# Power.net
KiCad netlist of a schematic drawn in Altium Designer
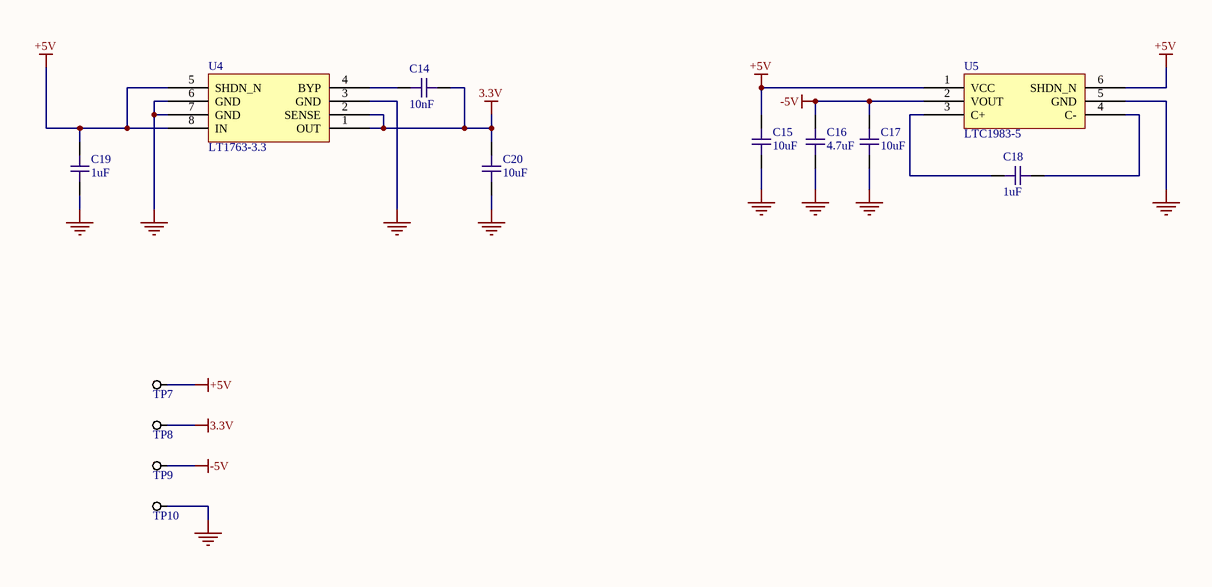
[diagram p0: Power.SchDoc]

(export (version "E")
  (design (tool "Eeschema 10.0.6"))
  (components
    (comp (ref "C14")
      (value "10nF")
      (footprint "C0402-IPC")
      (description "Chip Capacitor, 0402, 10nF, 16V, X7R")
      (fields (field (name "Comment") "C0402 10nF 16V X7R"))
      (libsource (lib "Capacitors") (part "C0402 10nF 16V X7R"))
    )
    (comp (ref "C15")
      (value "10uF")
      (footprint "C0402-HIGH-DENSITY")
      (description "Chip Capacitor, 0402, 10uF, 10V, X5R")
      (fields (field (name "Comment") "C0402 10uF 10V"))
      (libsource (lib "Capacitors") (part "C0402 10uF 10V"))
    )
    (comp (ref "C16")
      (value "4.7uF")
      (footprint "C0603-HIGH-DENSITY")
      (description "Chip Capacitor, 0603, 4.7uF, 25V, X5R")
      (fields (field (name "Comment") "4.7uF, 25V, X5R, 0603"))
      (libsource (lib "Capacitors") (part "C0603 4.7uF 25V X5R"))
    )
    (comp (ref "C17")
      (value "10uF")
      (footprint "C0402-HIGH-DENSITY")
      (description "Chip Capacitor, 0402, 10uF, 10V, X5R")
      (fields (field (name "Comment") "C0402 10uF 10V"))
      (libsource (lib "Capacitors") (part "C0402 10uF 10V"))
    )
    (comp (ref "C18")
      (value "1uF")
      (footprint "C0603-HIGH-DENSITY")
      (description "CAP CER 1UF 35V X5R 0603")
      (fields
        (field (name "MANUFACTURER") "Taiyo Yuden")
        (field (name "MANUFACTURER PART NUMBER") "GMK107BJ105MAHT")
      )
      (libsource (lib "AFE") (part "1uF 0603 35V X5R"))
    )
    (comp (ref "C19")
      (value "1uF")
      (footprint "C0603-HIGH-DENSITY")
      (description "CAP CER 1UF 35V X5R 0603")
      (fields
        (field (name "MANUFACTURER") "Taiyo Yuden")
        (field (name "MANUFACTURER PART NUMBER") "GMK107BJ105MAHT")
      )
      (libsource (lib "AFE") (part "1uF 0603 35V X5R"))
    )
    (comp (ref "C20")
      (value "10uF")
      (footprint "C0402-HIGH-DENSITY")
      (description "Chip Capacitor, 0402, 10uF, 10V, X5R")
      (fields (field (name "Comment") "C0402 10uF 10V"))
      (libsource (lib "Capacitors") (part "C0402 10uF 10V"))
    )
    (comp (ref "TP7")
      (value "Testpoint_TH")
      (footprint "Testpoint_TH")
      (description "Through-hole testpoint hook")
      (libsource (lib "Virtual Parts") (part "Testpoint_TH"))
    )
    (comp (ref "TP8")
      (value "Testpoint_TH")
      (footprint "Testpoint_TH")
      (description "Through-hole testpoint hook")
      (libsource (lib "Virtual Parts") (part "Testpoint_TH"))
    )
    (comp (ref "TP9")
      (value "Testpoint_TH")
      (footprint "Testpoint_TH")
      (description "Through-hole testpoint hook")
      (libsource (lib "Virtual Parts") (part "Testpoint_TH"))
    )
    (comp (ref "TP10")
      (value "Testpoint_TH")
      (footprint "Testpoint_TH")
      (description "Through-hole testpoint hook")
      (libsource (lib "Virtual Parts") (part "Testpoint_TH"))
    )
    (comp (ref "U4")
      (value "LT1763-3.3")
      (footprint "LT1763-3.3")
      (description "LDO Regulator Pos 3.3V 0.5A Automotive 8-Pin SOIC N Tube")
      (fields
        (field (name "MANUFACTURER") "Analog Devices / Linear Technology")
        (field (name "MANUFACTURER PART NUMBER") "LT1763CS8-3.3#PBF")
      )
      (libsource (lib "AFE") (part "LT1763-3.3"))
    )
    (comp (ref "U5")
      (value "LTC1983-5")
      (footprint "LTC1983-5")
      (description "IC REG SWTCHD CAP INV -5V SOT23")
      (fields
        (field (name "MANUFACTURER") "Analog Devices / Linear Technology")
        (field (name "MANUFACTURER PART NUMBER") "LTC1983ES6-5#TRPBF")
      )
      (libsource (lib "AFE") (part "LTC1983-5"))
    )
  )
  (nets
    (net (code "1") (name "+5V") (class "Default")
      (node (ref "C15") (pin "2") (pintype "passive"))
      (node (ref "C19") (pin "2") (pintype "passive"))
      (node (ref "TP7") (pin "1") (pinfunction "1_1") (pintype "passive"))
      (node (ref "U4") (pin "5") (pinfunction "SHDN_N_5") (pintype "passive"))
      (node (ref "U4") (pin "8") (pinfunction "IN_8") (pintype "passive"))
      (node (ref "U5") (pin "1") (pinfunction "VCC_1") (pintype "passive"))
      (node (ref "U5") (pin "6") (pinfunction "SHDN_N_6") (pintype "passive"))
    )
    (net (code "2") (name "-5V") (class "Default")
      (node (ref "C16") (pin "2") (pintype "passive"))
      (node (ref "C17") (pin "2") (pintype "passive"))
      (node (ref "TP9") (pin "1") (pinfunction "1_1") (pintype "passive"))
      (node (ref "U5") (pin "2") (pinfunction "VOUT_2") (pintype "passive"))
    )
    (net (code "3") (name "3.3V") (class "Default")
      (node (ref "C14") (pin "2") (pintype "passive"))
      (node (ref "C20") (pin "2") (pintype "passive"))
      (node (ref "TP8") (pin "1") (pinfunction "1_1") (pintype "passive"))
      (node (ref "U4") (pin "1") (pinfunction "OUT_1") (pintype "passive"))
      (node (ref "U4") (pin "2") (pinfunction "SENSE_2") (pintype "passive"))
    )
    (net (code "4") (name "GND") (class "Default")
      (node (ref "C15") (pin "1") (pintype "passive"))
      (node (ref "C16") (pin "1") (pintype "passive"))
      (node (ref "C17") (pin "1") (pintype "passive"))
      (node (ref "C19") (pin "1") (pintype "passive"))
      (node (ref "C20") (pin "1") (pintype "passive"))
      (node (ref "TP10") (pin "1") (pinfunction "1_1") (pintype "passive"))
      (node (ref "U4") (pin "3") (pinfunction "GND_3") (pintype "passive"))
      (node (ref "U4") (pin "6") (pinfunction "GND_6") (pintype "passive"))
      (node (ref "U4") (pin "7") (pinfunction "GND_7") (pintype "passive"))
      (node (ref "U5") (pin "5") (pinfunction "GND_5") (pintype "passive"))
    )
    (net (code "5") (name "Net-(U4-BYP)") (class "Default")
      (node (ref "C14") (pin "1") (pintype "passive"))
      (node (ref "U4") (pin "4") (pinfunction "BYP_4") (pintype "passive"))
    )
    (net (code "6") (name "Net-(U5-C+)") (class "Default")
      (node (ref "C18") (pin "1") (pintype "passive"))
      (node (ref "U5") (pin "3") (pinfunction "C+_3") (pintype "passive"))
    )
    (net (code "7") (name "Net-(U5-C-)") (class "Default")
      (node (ref "C18") (pin "2") (pintype "passive"))
      (node (ref "U5") (pin "4") (pinfunction "C-_4") (pintype "passive"))
    )
  )
)
